# SCH_PowerInOut.net
KiCad netlist of a schematic drawn in Altium Designer
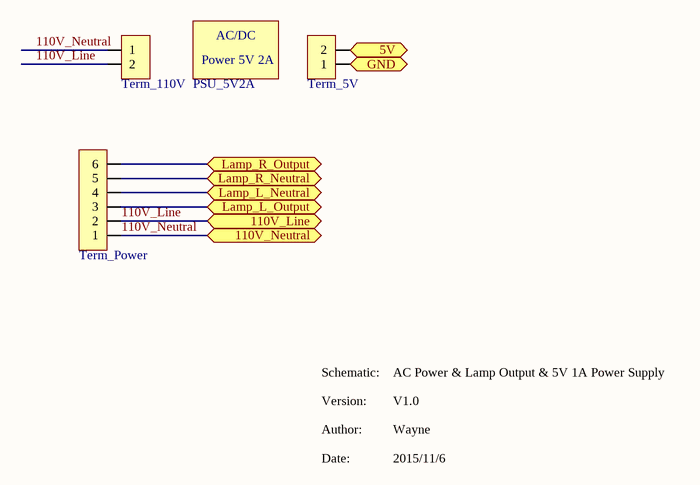
[diagram p0: SCH_PowerInOut.SchDoc]

(export (version "E")
  (design (tool "Eeschema 10.0.6"))
  (components
    (comp (ref "PSU_5V2A")
      (value "psu")
      (footprint "PCB_LIB:Power 5V2A Mechanical")
      (description "PSU AC DC 5V 2A Mechanical")
      (libsource (lib "SCH_LIB") (part "Psu 5V2A"))
    )
    (comp (ref "Term_5V")
      (value "Terminal Block Socket 2 way")
      (footprint "PCB_LIB:TermBlock Socket 2way 5.08")
      (description "Terminal Block Socket 2 way 5.08")
      (libsource (lib "") (part "Term Block Socket 2 way_1"))
    )
    (comp (ref "Term_110V")
      (value "Terminal Block Socket 2 way")
      (footprint "PCB_LIB:TermBlock Socket 2way 5.08")
      (description "Terminal Block Socket 2 way 5.08")
      (libsource (lib "SCH_LIB") (part "Term Block Socket 2 way"))
    )
    (comp (ref "Term_Power")
      (value "Terminal Block Socket 6 way")
      (footprint "PCB_LIB:TermBlock Socket 6way 5.08")
      (description "Terminal Block Socket 6 way 5.08")
      (libsource (lib "SCH_LIB") (part "Term Block Socket 6 way"))
    )
  )
  (nets
    (net (code "1") (name "/5V") (class "Default")
      (node (ref "Term_5V") (pin "2") (pinfunction "2_2") (pintype "passive"))
    )
    (net (code "2") (name "/110V_Line") (class "Default")
      (node (ref "Term_110V") (pin "2") (pinfunction "2_2") (pintype "passive"))
      (node (ref "Term_Power") (pin "2") (pinfunction "2_2") (pintype "passive"))
    )
    (net (code "3") (name "/110V_Neutral") (class "Default")
      (node (ref "Term_110V") (pin "1") (pinfunction "1_1") (pintype "passive"))
      (node (ref "Term_Power") (pin "1") (pinfunction "1_1") (pintype "passive"))
    )
    (net (code "4") (name "/GND") (class "Default")
      (node (ref "Term_5V") (pin "1") (pinfunction "1_1") (pintype "passive"))
    )
    (net (code "5") (name "/Lamp_L_Neutral") (class "Default")
      (node (ref "Term_Power") (pin "4") (pinfunction "4_4") (pintype "passive"))
    )
    (net (code "6") (name "/Lamp_L_Output") (class "Default")
      (node (ref "Term_Power") (pin "3") (pinfunction "3_3") (pintype "passive"))
    )
    (net (code "7") (name "/Lamp_R_Neutral") (class "Default")
      (node (ref "Term_Power") (pin "5") (pinfunction "5_5") (pintype "passive"))
    )
    (net (code "8") (name "/Lamp_R_Output") (class "Default")
      (node (ref "Term_Power") (pin "6") (pinfunction "6_6") (pintype "passive"))
    )
  )
)
